# atmega328p.net
KiCad netlist of a schematic drawn in EAGLE
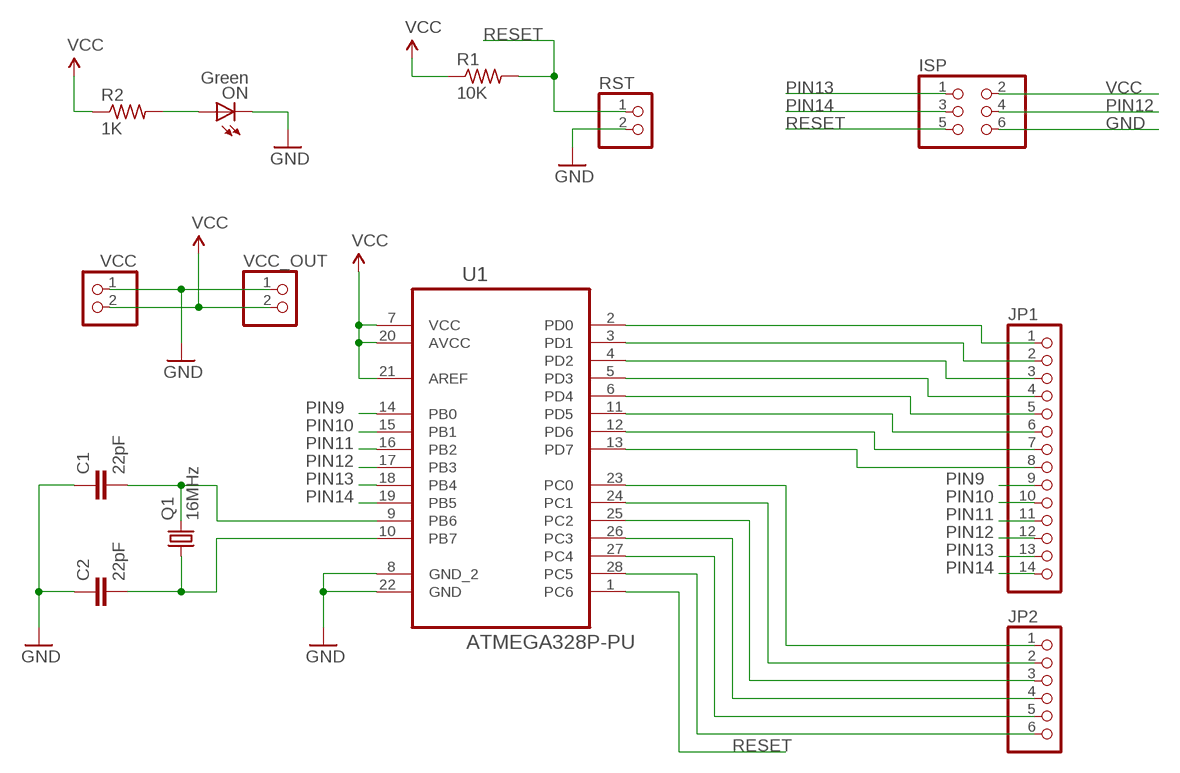
[diagram p0: schematic, sheet 1]

(export (version "E")
  (design (tool "Eeschema 10.0.6"))
  (components
    (comp (ref "C1")
      (value "22pF")
      (footprint "eagle-import:C0603")
      (libsource (lib "eagle-import") (part "C-EUC0603"))
    )
    (comp (ref "C2")
      (value "22pF")
      (footprint "eagle-import:C0603")
      (libsource (lib "eagle-import") (part "C-EUC0603"))
    )
    (comp (ref "ISP")
      (value "PINHD-2X3")
      (footprint "eagle-import:2X03")
      (libsource (lib "eagle-import") (part "PINHD-2X3"))
    )
    (comp (ref "JP1")
      (value "PINHD-1X14")
      (footprint "eagle-import:1X14")
      (libsource (lib "eagle-import") (part "PINHD-1X14"))
    )
    (comp (ref "JP2")
      (value "PINHD-1X6")
      (footprint "eagle-import:1X06")
      (libsource (lib "eagle-import") (part "PINHD-1X6"))
    )
    (comp (ref "ON")
      (value "Green")
      (footprint "eagle-import:CHIPLED_0805")
      (libsource (lib "eagle-import") (part "LEDCHIPLED_0805"))
    )
    (comp (ref "Q1")
      (value "16MHz")
      (footprint "eagle-import:HC49_S")
      (libsource (lib "eagle-import") (part "CRYSTALHC49S"))
    )
    (comp (ref "R1")
      (value "10K")
      (footprint "eagle-import:R0805")
      (libsource (lib "eagle-import") (part "R-US_R0805"))
    )
    (comp (ref "R2")
      (value "1K")
      (footprint "eagle-import:R0805")
      (libsource (lib "eagle-import") (part "R-US_R0805"))
    )
    (comp (ref "RST")
      (value "PINHD-1X2")
      (footprint "eagle-import:1X02")
      (libsource (lib "eagle-import") (part "PINHD-1X2"))
    )
    (comp (ref "U1")
      (value "ATMEGA328P-PU")
      (footprint "eagle-import:DIP254P762X457-28")
      (libsource (lib "eagle-import") (part "ATMEGA328P-PU"))
    )
    (comp (ref "VCC")
      (value "PINHD-1X2")
      (footprint "eagle-import:1X02")
      (libsource (lib "eagle-import") (part "PINHD-1X2"))
    )
    (comp (ref "VCC_OUT")
      (value "PINHD-1X2")
      (footprint "eagle-import:1X02")
      (libsource (lib "eagle-import") (part "PINHD-1X2"))
    )
  )
  (nets
    (net (code "1") (name "/PIN9") (class "Default")
      (node (ref "JP1") (pin "9") (pinfunction "9_9") (pintype "passive"))
      (node (ref "U1") (pin "14") (pinfunction "PB0_14") (pintype "bidirectional"))
    )
    (net (code "2") (name "/PIN10") (class "Default")
      (node (ref "JP1") (pin "10") (pinfunction "10_10") (pintype "passive"))
      (node (ref "U1") (pin "15") (pinfunction "PB1_15") (pintype "bidirectional"))
    )
    (net (code "3") (name "/PIN11") (class "Default")
      (node (ref "JP1") (pin "11") (pinfunction "11_11") (pintype "passive"))
      (node (ref "U1") (pin "16") (pinfunction "PB2_16") (pintype "bidirectional"))
    )
    (net (code "4") (name "/PIN12") (class "Default")
      (node (ref "ISP") (pin "4") (pinfunction "4_4") (pintype "passive"))
      (node (ref "JP1") (pin "12") (pinfunction "12_12") (pintype "passive"))
      (node (ref "U1") (pin "17") (pinfunction "PB3_17") (pintype "bidirectional"))
    )
    (net (code "5") (name "/PIN13") (class "Default")
      (node (ref "ISP") (pin "1") (pinfunction "1_1") (pintype "passive"))
      (node (ref "JP1") (pin "13") (pinfunction "13_13") (pintype "passive"))
      (node (ref "U1") (pin "18") (pinfunction "PB4_18") (pintype "bidirectional"))
    )
    (net (code "6") (name "/PIN14") (class "Default")
      (node (ref "ISP") (pin "3") (pinfunction "3_3") (pintype "passive"))
      (node (ref "JP1") (pin "14") (pinfunction "14_14") (pintype "passive"))
      (node (ref "U1") (pin "19") (pinfunction "PB5_19") (pintype "bidirectional"))
    )
    (net (code "7") (name "/RESET") (class "Default")
      (node (ref "ISP") (pin "5") (pinfunction "5_5") (pintype "passive"))
      (node (ref "R1") (pin "2") (pinfunction "2_2") (pintype "passive"))
      (node (ref "RST") (pin "1") (pinfunction "1_1") (pintype "passive"))
      (node (ref "U1") (pin "1") (pinfunction "PC6_1") (pintype "bidirectional"))
    )
    (net (code "8") (name "GND") (class "Default")
      (node (ref "C1") (pin "1") (pinfunction "1_1") (pintype "passive"))
      (node (ref "C2") (pin "1") (pinfunction "1_1") (pintype "passive"))
      (node (ref "ISP") (pin "6") (pinfunction "6_6") (pintype "passive"))
      (node (ref "ON") (pin "C") (pinfunction "C_C") (pintype "passive"))
      (node (ref "RST") (pin "2") (pinfunction "2_2") (pintype "passive"))
      (node (ref "U1") (pin "22") (pinfunction "GND_22") (pintype "passive"))
      (node (ref "U1") (pin "8") (pinfunction "GND_2_8") (pintype "passive"))
      (node (ref "VCC") (pin "1") (pinfunction "1_1") (pintype "passive"))
      (node (ref "VCC_OUT") (pin "1") (pinfunction "1_1") (pintype "passive"))
    )
    (net (code "9") (name "Net-(ON-PadA)") (class "Default")
      (node (ref "ON") (pin "A") (pinfunction "A_A") (pintype "passive"))
      (node (ref "R2") (pin "2") (pinfunction "2_2") (pintype "passive"))
    )
    (net (code "10") (name "Net-(U1-PB6)") (class "Default")
      (node (ref "C1") (pin "2") (pinfunction "2_2") (pintype "passive"))
      (node (ref "Q1") (pin "2") (pinfunction "2_2") (pintype "passive"))
      (node (ref "U1") (pin "9") (pinfunction "PB6_9") (pintype "bidirectional"))
    )
    (net (code "11") (name "Net-(U1-PB7)") (class "Default")
      (node (ref "C2") (pin "2") (pinfunction "2_2") (pintype "passive"))
      (node (ref "Q1") (pin "1") (pinfunction "1_1") (pintype "passive"))
      (node (ref "U1") (pin "10") (pinfunction "PB7_10") (pintype "bidirectional"))
    )
    (net (code "12") (name "Net-(U1-PC0)") (class "Default")
      (node (ref "JP2") (pin "1") (pinfunction "1_1") (pintype "passive"))
      (node (ref "U1") (pin "23") (pinfunction "PC0_23") (pintype "bidirectional"))
    )
    (net (code "13") (name "Net-(U1-PC1)") (class "Default")
      (node (ref "JP2") (pin "2") (pinfunction "2_2") (pintype "passive"))
      (node (ref "U1") (pin "24") (pinfunction "PC1_24") (pintype "bidirectional"))
    )
    (net (code "14") (name "Net-(U1-PC2)") (class "Default")
      (node (ref "JP2") (pin "3") (pinfunction "3_3") (pintype "passive"))
      (node (ref "U1") (pin "25") (pinfunction "PC2_25") (pintype "bidirectional"))
    )
    (net (code "15") (name "Net-(U1-PC3)") (class "Default")
      (node (ref "JP2") (pin "4") (pinfunction "4_4") (pintype "passive"))
      (node (ref "U1") (pin "26") (pinfunction "PC3_26") (pintype "bidirectional"))
    )
    (net (code "16") (name "Net-(U1-PC4)") (class "Default")
      (node (ref "JP2") (pin "5") (pinfunction "5_5") (pintype "passive"))
      (node (ref "U1") (pin "27") (pinfunction "PC4_27") (pintype "bidirectional"))
    )
    (net (code "17") (name "Net-(U1-PC5)") (class "Default")
      (node (ref "JP2") (pin "6") (pinfunction "6_6") (pintype "passive"))
      (node (ref "U1") (pin "28") (pinfunction "PC5_28") (pintype "bidirectional"))
    )
    (net (code "18") (name "Net-(U1-PD0)") (class "Default")
      (node (ref "JP1") (pin "1") (pinfunction "1_1") (pintype "passive"))
      (node (ref "U1") (pin "2") (pinfunction "PD0_2") (pintype "bidirectional"))
    )
    (net (code "19") (name "Net-(U1-PD1)") (class "Default")
      (node (ref "JP1") (pin "2") (pinfunction "2_2") (pintype "passive"))
      (node (ref "U1") (pin "3") (pinfunction "PD1_3") (pintype "bidirectional"))
    )
    (net (code "20") (name "Net-(U1-PD2)") (class "Default")
      (node (ref "JP1") (pin "3") (pinfunction "3_3") (pintype "passive"))
      (node (ref "U1") (pin "4") (pinfunction "PD2_4") (pintype "bidirectional"))
    )
    (net (code "21") (name "Net-(U1-PD3)") (class "Default")
      (node (ref "JP1") (pin "4") (pinfunction "4_4") (pintype "passive"))
      (node (ref "U1") (pin "5") (pinfunction "PD3_5") (pintype "bidirectional"))
    )
    (net (code "22") (name "Net-(U1-PD4)") (class "Default")
      (node (ref "JP1") (pin "5") (pinfunction "5_5") (pintype "passive"))
      (node (ref "U1") (pin "6") (pinfunction "PD4_6") (pintype "bidirectional"))
    )
    (net (code "23") (name "Net-(U1-PD5)") (class "Default")
      (node (ref "JP1") (pin "6") (pinfunction "6_6") (pintype "passive"))
      (node (ref "U1") (pin "11") (pinfunction "PD5_11") (pintype "bidirectional"))
    )
    (net (code "24") (name "Net-(U1-PD6)") (class "Default")
      (node (ref "JP1") (pin "7") (pinfunction "7_7") (pintype "passive"))
      (node (ref "U1") (pin "12") (pinfunction "PD6_12") (pintype "bidirectional"))
    )
    (net (code "25") (name "Net-(U1-PD7)") (class "Default")
      (node (ref "JP1") (pin "8") (pinfunction "8_8") (pintype "passive"))
      (node (ref "U1") (pin "13") (pinfunction "PD7_13") (pintype "bidirectional"))
    )
    (net (code "26") (name "VCC") (class "Default")
      (node (ref "ISP") (pin "2") (pinfunction "2_2") (pintype "passive"))
      (node (ref "R1") (pin "1") (pinfunction "1_1") (pintype "passive"))
      (node (ref "R2") (pin "1") (pinfunction "1_1") (pintype "passive"))
      (node (ref "U1") (pin "20") (pinfunction "AVCC_20") (pintype "power_in"))
      (node (ref "U1") (pin "21") (pinfunction "AREF_21") (pintype "input"))
      (node (ref "U1") (pin "7") (pinfunction "VCC_7") (pintype "power_in"))
      (node (ref "VCC") (pin "2") (pinfunction "2_2") (pintype "passive"))
      (node (ref "VCC_OUT") (pin "2") (pinfunction "2_2") (pintype "passive"))
    )
  )
)
